# SCH_analog_2025-01-25.net
KiCad netlist of a schematic drawn in EasyEDA
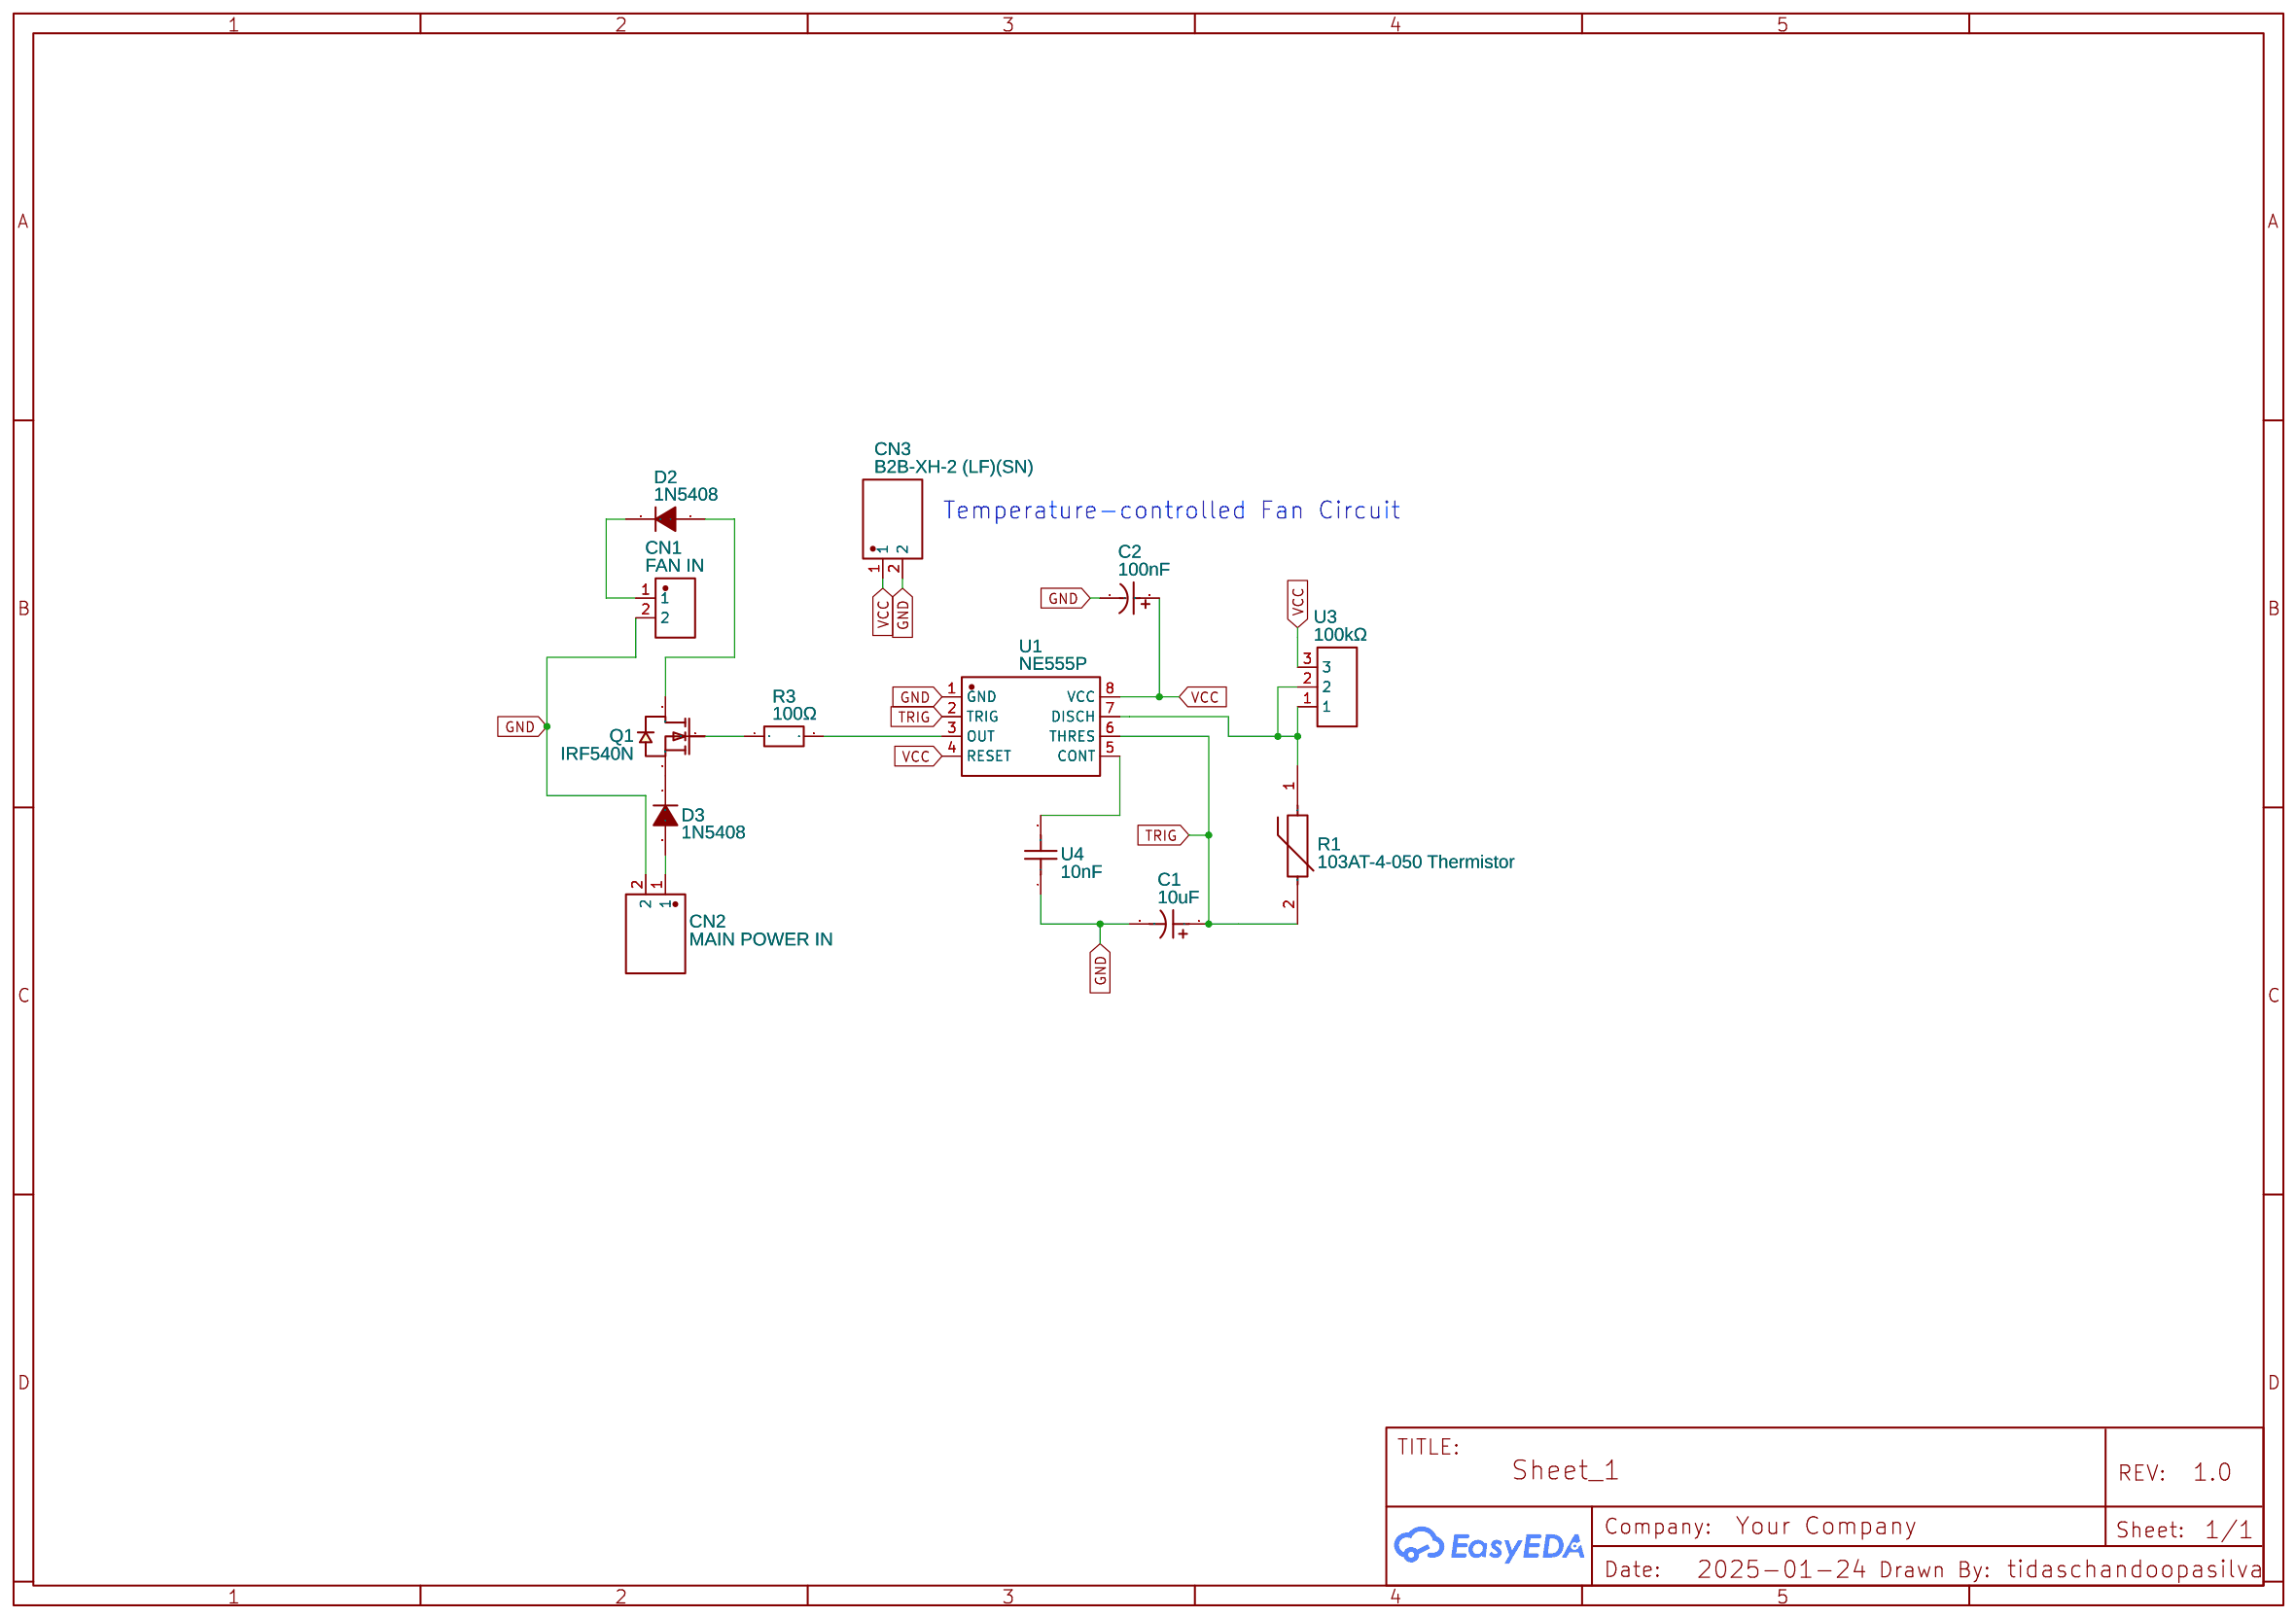
[diagram p0: schematic sheet]

(export (version "E")
  (design (tool "Eeschema 10.0.6"))
  (components
    (comp (ref "C1")
      (value "10uF")
      (fields (field (name "Manufacturer Part") "KM1V101M0812") (field (name "Manufacturer") "ROQANG(容强)"))
      (libsource (lib "") (part "KM1V101M0812"))
    )
    (comp (ref "C2")
      (value "100nF")
      (fields
        (field (name "Manufacturer Part") "KM104M050D11RR0VH2FP0")
        (field (name "Manufacturer") "CX(承兴)")
      )
      (libsource (lib "") (part "0.1UF 50V"))
    )
    (comp (ref "CN1")
      (value "FAN IN")
      (fields
        (field (name "Manufacturer Part") "1729128")
        (field (name "Manufacturer") "Phoenix Contact(菲尼克斯)")
      )
      (libsource (lib "") (part "1729128"))
    )
    (comp (ref "CN2")
      (value "MAIN POWER IN")
      (fields (field (name "Manufacturer Part") "B2B-XH-2(LF)(SN)") (field (name "Manufacturer") "JST"))
      (libsource (lib "") (part "B2B-XH-2 (LF)(SN)_1"))
    )
    (comp (ref "CN3")
      (value "B2B-XH-2 (LF)(SN)")
      (fields (field (name "Manufacturer Part") "B2B-XH-2(LF)(SN)") (field (name "Manufacturer") "JST"))
      (libsource (lib "") (part "B2B-XH-2 (LF)(SN)"))
    )
    (comp (ref "D2")
      (value "1N5408")
      (fields (field (name "Manufacturer") "MDD(辰达半导体)"))
      (libsource (lib "") (part "1N5408-C2460_1"))
    )
    (comp (ref "D3")
      (value "1N5408")
      (fields (field (name "Manufacturer") "MDD(辰达半导体)"))
      (libsource (lib "") (part "1N5408-C2460"))
    )
    (comp (ref "Q1")
      (value "IRF540N")
      (fields (field (name "Manufacturer Part") "IRF540N-VB") (field (name "Manufacturer") "VBsemi(微碧半导体)"))
      (libsource (lib "") (part "IRF540N"))
    )
    (comp (ref "R1")
      (value "103AT-4-050 Thermistor")
      (fields (field (name "Manufacturer Part") "103AT-4-050") (field (name "Manufacturer") "semitec(石冢)"))
      (libsource (lib "") (part "103AT-4-050"))
    )
    (comp (ref "R3")
      (value "100Ω")
      (fields
        (field (name "Manufacturer Part") "RD 1/4W 100R J T/B A1")
        (field (name "Manufacturer") "Tyohm(幸亚电阻)")
      )
      (libsource (lib "") (part "RD 1/4W 100R J T/B A1"))
    )
    (comp (ref "U1")
      (value "NE555P")
      (fields (field (name "Manufacturer") "TI(德州仪器)"))
      (libsource (lib "") (part "NE555P"))
    )
    (comp (ref "U3")
      (value "100kΩ")
      (fields
        (field (name "Manufacturer Part") "RK2711120026")
        (field (name "Manufacturer") "ALPSALPINE(阿尔卑斯阿尔派)")
      )
      (libsource (lib "") (part "RK2711120026"))
    )
    (comp (ref "U4")
      (value "10nF")
      (fields (field (name "Manufacturer Part") "FK14C0G1H103J") (field (name "Manufacturer") "TDK"))
      (libsource (lib "") (part "FK14C0G1H103J"))
    )
  )
  (nets
    (net (code "1") (name "GND") (class "Default")
      (node (ref "C1") (pin "2") (pinfunction "2_2") (pintype "input"))
      (node (ref "C2") (pin "2") (pinfunction "2_2") (pintype "input"))
      (node (ref "CN1") (pin "2") (pinfunction "2_2") (pintype "unspecified"))
      (node (ref "CN2") (pin "2") (pinfunction "2_2") (pintype "unspecified"))
      (node (ref "CN3") (pin "2") (pinfunction "2_2") (pintype "unspecified"))
      (node (ref "U1") (pin "1") (pinfunction "GND_1") (pintype "unspecified"))
      (node (ref "U4") (pin "1") (pinfunction "1_1") (pintype "unspecified"))
    )
    (net (code "2") (name "Net-(D2-A)") (class "Default")
      (node (ref "D2") (pin "2") (pinfunction "A_2") (pintype "unspecified"))
      (node (ref "Q1") (pin "2") (pinfunction "D_2") (pintype "unspecified"))
    )
    (net (code "3") (name "Net-(D2-C)") (class "Default")
      (node (ref "CN1") (pin "1") (pinfunction "1_1") (pintype "unspecified"))
      (node (ref "D2") (pin "1") (pinfunction "C_1") (pintype "unspecified"))
    )
    (net (code "4") (name "Net-(D3-A)") (class "Default")
      (node (ref "CN2") (pin "1") (pinfunction "1_1") (pintype "unspecified"))
      (node (ref "D3") (pin "2") (pinfunction "A_2") (pintype "unspecified"))
    )
    (net (code "5") (name "Net-(D3-C)") (class "Default")
      (node (ref "D3") (pin "1") (pinfunction "C_1") (pintype "unspecified"))
      (node (ref "Q1") (pin "3") (pinfunction "S_3") (pintype "unspecified"))
    )
    (net (code "6") (name "Net-(Q1-G)") (class "Default")
      (node (ref "Q1") (pin "1") (pinfunction "G_1") (pintype "unspecified"))
      (node (ref "R3") (pin "1") (pinfunction "1_1") (pintype "unspecified"))
    )
    (net (code "7") (name "Net-(U1-CONT)") (class "Default")
      (node (ref "U1") (pin "5") (pinfunction "CONT_5") (pintype "unspecified"))
      (node (ref "U4") (pin "2") (pinfunction "2_2") (pintype "unspecified"))
    )
    (net (code "8") (name "Net-(U1-DISCH)") (class "Default")
      (node (ref "R1") (pin "1") (pinfunction "1_1") (pintype "unspecified"))
      (node (ref "U1") (pin "7") (pinfunction "DISCH_7") (pintype "unspecified"))
      (node (ref "U3") (pin "1") (pinfunction "1_1") (pintype "unspecified"))
      (node (ref "U3") (pin "2") (pinfunction "2_2") (pintype "unspecified"))
    )
    (net (code "9") (name "Net-(U1-OUT)") (class "Default")
      (node (ref "R3") (pin "2") (pinfunction "2_2") (pintype "unspecified"))
      (node (ref "U1") (pin "3") (pinfunction "OUT_3") (pintype "unspecified"))
    )
    (net (code "10") (name "TRIG") (class "Default")
      (node (ref "C1") (pin "1") (pinfunction "1_1") (pintype "input"))
      (node (ref "R1") (pin "2") (pinfunction "2_2") (pintype "unspecified"))
      (node (ref "U1") (pin "2") (pinfunction "TRIG_2") (pintype "unspecified"))
      (node (ref "U1") (pin "6") (pinfunction "THRES_6") (pintype "unspecified"))
    )
    (net (code "11") (name "VCC") (class "Default")
      (node (ref "C2") (pin "1") (pinfunction "1_1") (pintype "input"))
      (node (ref "CN3") (pin "1") (pinfunction "1_1") (pintype "unspecified"))
      (node (ref "U1") (pin "4") (pinfunction "RESET_4") (pintype "unspecified"))
      (node (ref "U1") (pin "8") (pinfunction "VCC_8") (pintype "unspecified"))
      (node (ref "U3") (pin "3") (pinfunction "3_3") (pintype "unspecified"))
    )
  )
)
